# TAG.net
KiCad netlist of a schematic drawn in Altium Designer
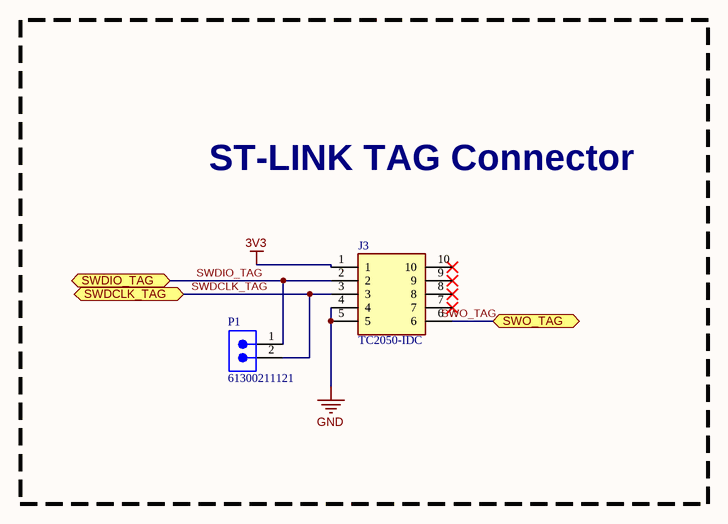
[diagram p0: TAG.SchDoc]

(export (version "E")
  (design (tool "Eeschema 10.0.6"))
  (components
    (comp (ref "J3")
      (value "TC2050-IDC")
      (footprint "TC2050-IDC")
      (description "Connector")
      (libsource (lib "C2S") (part "TC2050-IDC"))
    )
    (comp (ref "P1")
      (value "61300211121")
      (footprint "61300211121")
      (description "WR-PHD Pin Header, THT, Vertical, pitch 2.54mm, 1 Row, 2P")
      (fields (field (name "MANUFACTURER") "Wurth Elektronik"))
      (libsource (lib "Perth Aerospace Student Team") (part "62000211121"))
    )
  )
  (nets
    (net (code "1") (name "/SWDCLK_TAG") (class "Default")
      (node (ref "J3") (pin "3") (pinfunction "3_3") (pintype "passive"))
      (node (ref "P1") (pin "2") (pinfunction "2_2") (pintype "passive"))
    )
    (net (code "2") (name "/SWDIO_TAG") (class "Default")
      (node (ref "J3") (pin "2") (pinfunction "2_2") (pintype "passive"))
      (node (ref "P1") (pin "1") (pinfunction "1_1") (pintype "passive"))
    )
    (net (code "3") (name "/SWO_TAG") (class "Default")
      (node (ref "J3") (pin "6") (pinfunction "6_6") (pintype "passive"))
    )
    (net (code "4") (name "3V3") (class "Default")
      (node (ref "J3") (pin "1") (pinfunction "1_1") (pintype "passive"))
    )
    (net (code "5") (name "GND") (class "Default")
      (node (ref "J3") (pin "4") (pinfunction "4_4") (pintype "passive"))
      (node (ref "J3") (pin "5") (pinfunction "5_5") (pintype "passive"))
    )
    (net (code "6") (name "unconnected-(J3-Pad7)") (class "Default")
      (node (ref "J3") (pin "7") (pinfunction "7_7") (pintype "passive+no_connect"))
    )
    (net (code "7") (name "unconnected-(J3-Pad8)") (class "Default")
      (node (ref "J3") (pin "8") (pinfunction "8_8") (pintype "passive+no_connect"))
    )
    (net (code "8") (name "unconnected-(J3-Pad9)") (class "Default")
      (node (ref "J3") (pin "9") (pinfunction "9_9") (pintype "passive+no_connect"))
    )
    (net (code "9") (name "unconnected-(J3-Pad10)") (class "Default")
      (node (ref "J3") (pin "10") (pinfunction "10_10") (pintype "passive+no_connect"))
    )
  )
)
